# MCP1700.net
KiCad netlist of a schematic drawn in EAGLE
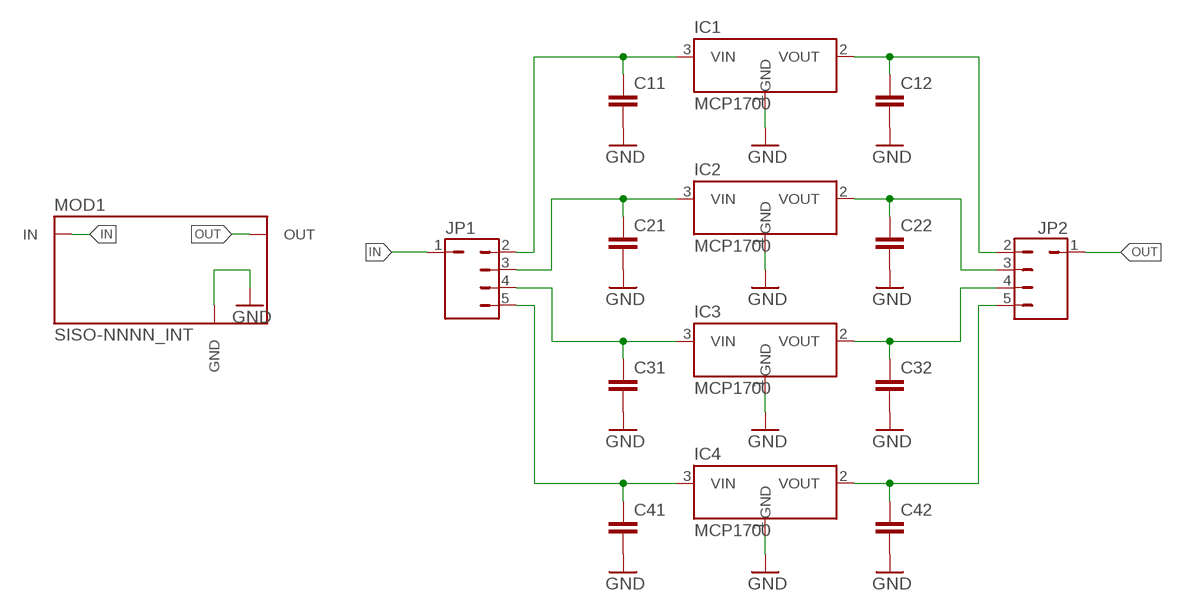
[diagram p0: schematic, sheet 1]

(export (version "E")
  (design (tool "Eeschema 10.0.6"))
  (components
    (comp (ref "C11")
      (value "C-EUC0805")
      (footprint "eagle-import:C0805")
      (libsource (lib "eagle-import") (part "C-EUC0805"))
    )
    (comp (ref "C12")
      (value "C-EUC0805")
      (footprint "eagle-import:C0805")
      (libsource (lib "eagle-import") (part "C-EUC0805"))
    )
    (comp (ref "C21")
      (value "C-EUC0805")
      (footprint "eagle-import:C0805")
      (libsource (lib "eagle-import") (part "C-EUC0805"))
    )
    (comp (ref "C22")
      (value "C-EUC0805")
      (footprint "eagle-import:C0805")
      (libsource (lib "eagle-import") (part "C-EUC0805"))
    )
    (comp (ref "C31")
      (value "C-EUC0805")
      (footprint "eagle-import:C0805")
      (libsource (lib "eagle-import") (part "C-EUC0805"))
    )
    (comp (ref "C32")
      (value "C-EUC0805")
      (footprint "eagle-import:C0805")
      (libsource (lib "eagle-import") (part "C-EUC0805"))
    )
    (comp (ref "C41")
      (value "C-EUC0805")
      (footprint "eagle-import:C0805")
      (libsource (lib "eagle-import") (part "C-EUC0805"))
    )
    (comp (ref "C42")
      (value "C-EUC0805")
      (footprint "eagle-import:C0805")
      (libsource (lib "eagle-import") (part "C-EUC0805"))
    )
    (comp (ref "IC1")
      (value "MCP1700")
      (footprint "eagle-import:SOT23")
      (libsource (lib "eagle-import") (part "MCP1700"))
    )
    (comp (ref "IC2")
      (value "MCP1700")
      (footprint "eagle-import:SOT23")
      (libsource (lib "eagle-import") (part "MCP1700"))
    )
    (comp (ref "IC3")
      (value "MCP1700")
      (footprint "eagle-import:SOT23")
      (libsource (lib "eagle-import") (part "MCP1700"))
    )
    (comp (ref "IC4")
      (value "MCP1700")
      (footprint "eagle-import:SOT23")
      (libsource (lib "eagle-import") (part "MCP1700"))
    )
    (comp (ref "JP1")
      (value "JP4Q")
      (footprint "eagle-import:JP1-4")
      (libsource (lib "eagle-import") (part "JP4Q"))
    )
    (comp (ref "JP2")
      (value "JP4Q")
      (footprint "eagle-import:JP1-4")
      (libsource (lib "eagle-import") (part "JP4Q"))
    )
    (comp (ref "MOD1")
      (value "SISO-NNNN_INT")
      (footprint "eagle-import:SISO-NNNN")
      (libsource (lib "eagle-import") (part "SISO-NNNN_INT"))
    )
  )
  (nets
    (net (code "1") (name "GND") (class "Default")
      (node (ref "C11") (pin "2") (pinfunction "2_2") (pintype "passive"))
      (node (ref "C12") (pin "2") (pinfunction "2_2") (pintype "passive"))
      (node (ref "C21") (pin "2") (pinfunction "2_2") (pintype "passive"))
      (node (ref "C22") (pin "2") (pinfunction "2_2") (pintype "passive"))
      (node (ref "C31") (pin "2") (pinfunction "2_2") (pintype "passive"))
      (node (ref "C32") (pin "2") (pinfunction "2_2") (pintype "passive"))
      (node (ref "C41") (pin "2") (pinfunction "2_2") (pintype "passive"))
      (node (ref "C42") (pin "2") (pinfunction "2_2") (pintype "passive"))
      (node (ref "IC1") (pin "1") (pinfunction "GND_1") (pintype "power_in"))
      (node (ref "IC2") (pin "1") (pinfunction "GND_1") (pintype "power_in"))
      (node (ref "IC3") (pin "1") (pinfunction "GND_1") (pintype "power_in"))
      (node (ref "IC4") (pin "1") (pinfunction "GND_1") (pintype "power_in"))
      (node (ref "MOD1") (pin "GND1") (pinfunction "GND_GND1") (pintype "power_in"))
      (node (ref "MOD1") (pin "GND2") (pinfunction "GND_GND2") (pintype "power_in"))
      (node (ref "MOD1") (pin "GND3") (pinfunction "GND_GND3") (pintype "power_in"))
      (node (ref "MOD1") (pin "GND4") (pinfunction "GND_GND4") (pintype "power_in"))
    )
    (net (code "2") (name "IN") (class "Default")
      (node (ref "JP1") (pin "1") (pinfunction "1_1") (pintype "passive"))
      (node (ref "MOD1") (pin "IN1") (pinfunction "IN_IN1") (pintype "input"))
      (node (ref "MOD1") (pin "IN2") (pinfunction "IN_IN2") (pintype "input"))
      (node (ref "MOD1") (pin "IN3") (pinfunction "IN_IN3") (pintype "input"))
      (node (ref "MOD1") (pin "IN4") (pinfunction "IN_IN4") (pintype "input"))
    )
    (net (code "3") (name "Net-(IC1-VIN)") (class "Default")
      (node (ref "C11") (pin "1") (pinfunction "1_1") (pintype "passive"))
      (node (ref "IC1") (pin "3") (pinfunction "VIN_3") (pintype "input"))
      (node (ref "JP1") (pin "2") (pinfunction "2_2") (pintype "passive"))
    )
    (net (code "4") (name "Net-(IC1-VOUT)") (class "Default")
      (node (ref "C12") (pin "1") (pinfunction "1_1") (pintype "passive"))
      (node (ref "IC1") (pin "2") (pinfunction "VOUT_2") (pintype "output"))
      (node (ref "JP2") (pin "2") (pinfunction "2_2") (pintype "passive"))
    )
    (net (code "5") (name "Net-(IC2-VIN)") (class "Default")
      (node (ref "C21") (pin "1") (pinfunction "1_1") (pintype "passive"))
      (node (ref "IC2") (pin "3") (pinfunction "VIN_3") (pintype "input"))
      (node (ref "JP1") (pin "3") (pinfunction "3_3") (pintype "passive"))
    )
    (net (code "6") (name "Net-(IC2-VOUT)") (class "Default")
      (node (ref "C22") (pin "1") (pinfunction "1_1") (pintype "passive"))
      (node (ref "IC2") (pin "2") (pinfunction "VOUT_2") (pintype "output"))
      (node (ref "JP2") (pin "3") (pinfunction "3_3") (pintype "passive"))
    )
    (net (code "7") (name "Net-(IC3-VIN)") (class "Default")
      (node (ref "C31") (pin "1") (pinfunction "1_1") (pintype "passive"))
      (node (ref "IC3") (pin "3") (pinfunction "VIN_3") (pintype "input"))
      (node (ref "JP1") (pin "4") (pinfunction "4_4") (pintype "passive"))
    )
    (net (code "8") (name "Net-(IC3-VOUT)") (class "Default")
      (node (ref "C32") (pin "1") (pinfunction "1_1") (pintype "passive"))
      (node (ref "IC3") (pin "2") (pinfunction "VOUT_2") (pintype "output"))
      (node (ref "JP2") (pin "4") (pinfunction "4_4") (pintype "passive"))
    )
    (net (code "9") (name "Net-(IC4-VIN)") (class "Default")
      (node (ref "C41") (pin "1") (pinfunction "1_1") (pintype "passive"))
      (node (ref "IC4") (pin "3") (pinfunction "VIN_3") (pintype "input"))
      (node (ref "JP1") (pin "5") (pinfunction "5_5") (pintype "passive"))
    )
    (net (code "10") (name "Net-(IC4-VOUT)") (class "Default")
      (node (ref "C42") (pin "1") (pinfunction "1_1") (pintype "passive"))
      (node (ref "IC4") (pin "2") (pinfunction "VOUT_2") (pintype "output"))
      (node (ref "JP2") (pin "5") (pinfunction "5_5") (pintype "passive"))
    )
    (net (code "11") (name "OUT") (class "Default")
      (node (ref "JP2") (pin "1") (pinfunction "1_1") (pintype "passive"))
      (node (ref "MOD1") (pin "OUT1") (pinfunction "OUT_OUT1") (pintype "output"))
      (node (ref "MOD1") (pin "OUT2") (pinfunction "OUT_OUT2") (pintype "output"))
      (node (ref "MOD1") (pin "OUT3") (pinfunction "OUT_OUT3") (pintype "output"))
      (node (ref "MOD1") (pin "OUT4") (pinfunction "OUT_OUT4") (pintype "output"))
    )
  )
)
